# Lynx.net
KiCad netlist of a schematic drawn in EAGLE
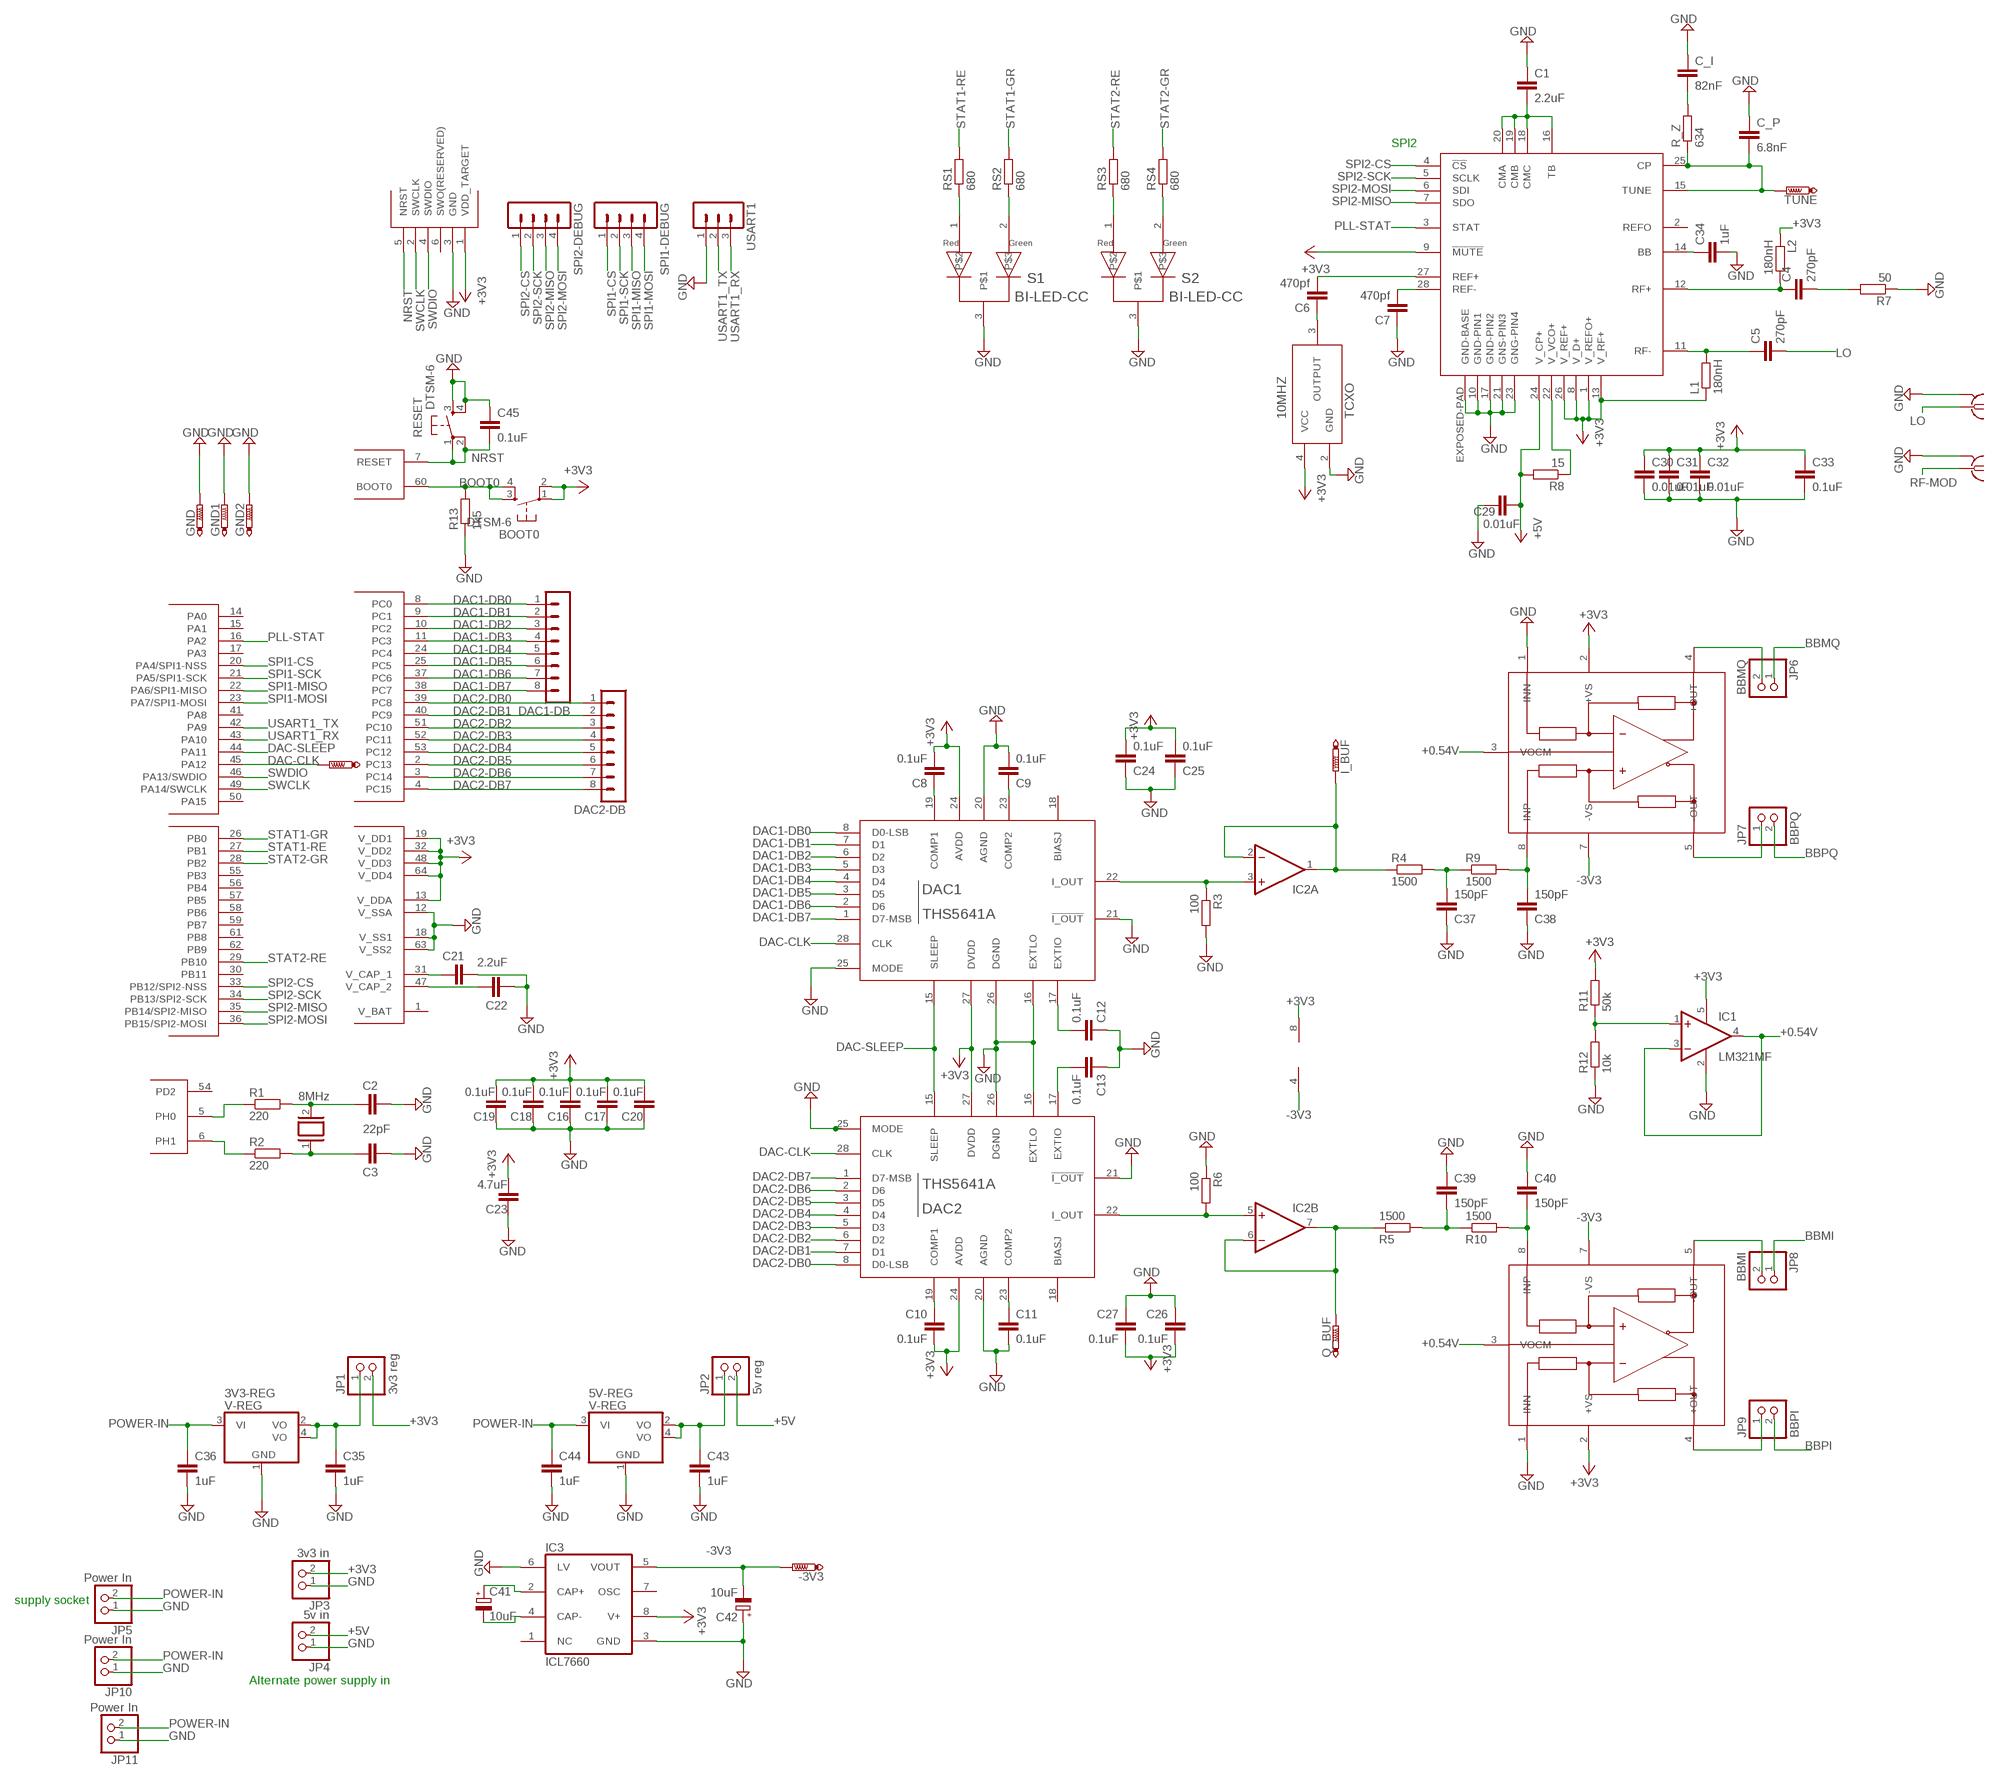
[diagram p0: schematic, sheet 1, part 1 of 2]
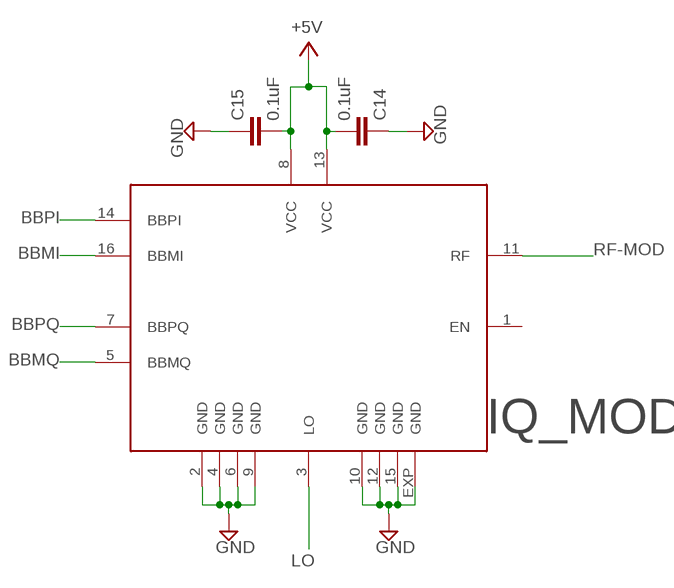
[diagram p1: schematic, sheet 1, part 2 of 2]

(export (version "E")
  (design (tool "Eeschema 10.0.6"))
  (components
    (comp (ref "-3V3")
      (value "PTR1PAD1-13Y")
      (footprint "eagle-import:P1-13Y")
      (libsource (lib "eagle-import") (part "PTR1PAD1-13Y"))
    )
    (comp (ref "3V3-REG")
      (value "V-REG")
      (footprint "eagle-import:SOT223")
      (libsource (lib "eagle-import") (part "VOLTAGE-REGULATOR"))
    )
    (comp (ref "5V-REG")
      (value "V-REG")
      (footprint "eagle-import:SOT223")
      (libsource (lib "eagle-import") (part "VOLTAGE-REGULATOR"))
    )
    (comp (ref "10MHZ")
      (value "TCXO")
      (footprint "eagle-import:TXCO5.6")
      (libsource (lib "eagle-import") (part "TCXO"))
    )
    (comp (ref "BOOT0")
      (value "DTSM-6")
      (footprint "eagle-import:DTSM-6")
      (libsource (lib "eagle-import") (part "DTSM-6"))
    )
    (comp (ref "C1")
      (value "2.2uF")
      (footprint "eagle-import:C0603")
      (libsource (lib "eagle-import") (part "C-EUC0603"))
    )
    (comp (ref "C2")
      (value "22pF")
      (footprint "eagle-import:C0603")
      (libsource (lib "eagle-import") (part "resistor_C-EUC0603"))
    )
    (comp (ref "C3")
      (value "22pF")
      (footprint "eagle-import:C0603")
      (libsource (lib "eagle-import") (part "resistor_C-EUC0603"))
    )
    (comp (ref "C4")
      (value "270pF")
      (footprint "eagle-import:C0805")
      (libsource (lib "eagle-import") (part "C-EUC0805"))
    )
    (comp (ref "C5")
      (value "270pF")
      (footprint "eagle-import:C0805")
      (libsource (lib "eagle-import") (part "C-EUC0805"))
    )
    (comp (ref "C6")
      (value "470pf")
      (footprint "eagle-import:C0402")
      (libsource (lib "eagle-import") (part "C-EUC0402"))
    )
    (comp (ref "C7")
      (value "470pf")
      (footprint "eagle-import:C0402")
      (libsource (lib "eagle-import") (part "C-EUC0402"))
    )
    (comp (ref "C8")
      (value "0.1uF")
      (footprint "eagle-import:C0603")
      (libsource (lib "eagle-import") (part "C-EUC0603"))
    )
    (comp (ref "C9")
      (value "0.1uF")
      (footprint "eagle-import:C0603")
      (libsource (lib "eagle-import") (part "C-EUC0603"))
    )
    (comp (ref "C10")
      (value "0.1uF")
      (footprint "eagle-import:C0603")
      (libsource (lib "eagle-import") (part "C-EUC0603"))
    )
    (comp (ref "C11")
      (value "0.1uF")
      (footprint "eagle-import:C0603")
      (libsource (lib "eagle-import") (part "C-EUC0603"))
    )
    (comp (ref "C12")
      (value "0.1uF")
      (footprint "eagle-import:C0603")
      (libsource (lib "eagle-import") (part "C-EUC0603"))
    )
    (comp (ref "C13")
      (value "0.1uF")
      (footprint "eagle-import:C0603")
      (libsource (lib "eagle-import") (part "C-EUC0603"))
    )
    (comp (ref "C14")
      (value "0.1uF")
      (footprint "eagle-import:C0603")
      (libsource (lib "eagle-import") (part "C-EUC0603"))
    )
    (comp (ref "C15")
      (value "0.1uF")
      (footprint "eagle-import:C0603")
      (libsource (lib "eagle-import") (part "C-EUC0603"))
    )
    (comp (ref "C16")
      (value "0.1uF")
      (footprint "eagle-import:C0603")
      (libsource (lib "eagle-import") (part "C-EUC0603"))
    )
    (comp (ref "C17")
      (value "0.1uF")
      (footprint "eagle-import:C0603")
      (libsource (lib "eagle-import") (part "C-EUC0603"))
    )
    (comp (ref "C18")
      (value "0.1uF")
      (footprint "eagle-import:C0603")
      (libsource (lib "eagle-import") (part "C-EUC0603"))
    )
    (comp (ref "C19")
      (value "0.1uF")
      (footprint "eagle-import:C0603")
      (libsource (lib "eagle-import") (part "C-EUC0603"))
    )
    (comp (ref "C20")
      (value "0.1uF")
      (footprint "eagle-import:C0603")
      (libsource (lib "eagle-import") (part "C-EUC0603"))
    )
    (comp (ref "C21")
      (value "2.2uF")
      (footprint "eagle-import:C0603")
      (libsource (lib "eagle-import") (part "resistor_C-EUC0603"))
    )
    (comp (ref "C22")
      (value "2.2uF")
      (footprint "eagle-import:C0603")
      (libsource (lib "eagle-import") (part "resistor_C-EUC0603"))
    )
    (comp (ref "C23")
      (value "4.7uF")
      (footprint "eagle-import:C0603")
      (libsource (lib "eagle-import") (part "C-EUC0603"))
    )
    (comp (ref "C24")
      (value "0.1uF")
      (footprint "eagle-import:C0603")
      (libsource (lib "eagle-import") (part "C-EUC0603"))
    )
    (comp (ref "C25")
      (value "0.1uF")
      (footprint "eagle-import:C0603")
      (libsource (lib "eagle-import") (part "C-EUC0603"))
    )
    (comp (ref "C26")
      (value "0.1uF")
      (footprint "eagle-import:C0603")
      (libsource (lib "eagle-import") (part "C-EUC0603"))
    )
    (comp (ref "C27")
      (value "0.1uF")
      (footprint "eagle-import:C0603")
      (libsource (lib "eagle-import") (part "C-EUC0603"))
    )
    (comp (ref "C29")
      (value "0.01uF")
      (footprint "eagle-import:C0603")
      (libsource (lib "eagle-import") (part "C-EUC0603"))
    )
    (comp (ref "C30")
      (value "0.01uF")
      (footprint "eagle-import:C0603")
      (libsource (lib "eagle-import") (part "C-EUC0603"))
    )
    (comp (ref "C31")
      (value "0.01uF")
      (footprint "eagle-import:C0402")
      (libsource (lib "eagle-import") (part "C-EUC0402"))
    )
    (comp (ref "C32")
      (value "0.01uF")
      (footprint "eagle-import:C0603")
      (libsource (lib "eagle-import") (part "C-EUC0603"))
    )
    (comp (ref "C33")
      (value "0.1uF")
      (footprint "eagle-import:C0603")
      (libsource (lib "eagle-import") (part "C-EUC0603"))
    )
    (comp (ref "C34")
      (value "1uF")
      (footprint "eagle-import:C0603")
      (libsource (lib "eagle-import") (part "C-EUC0603"))
    )
    (comp (ref "C35")
      (value "1uF")
      (footprint "eagle-import:C0603")
      (libsource (lib "eagle-import") (part "C-EUC0603"))
    )
    (comp (ref "C36")
      (value "1uF")
      (footprint "eagle-import:C0603")
      (libsource (lib "eagle-import") (part "C-EUC0603"))
    )
    (comp (ref "C37")
      (value "150pF")
      (footprint "eagle-import:C0603")
      (libsource (lib "eagle-import") (part "C-EUC0603"))
    )
    (comp (ref "C38")
      (value "150pF")
      (footprint "eagle-import:C0603")
      (libsource (lib "eagle-import") (part "C-EUC0603"))
    )
    (comp (ref "C39")
      (value "150pF")
      (footprint "eagle-import:C0603")
      (libsource (lib "eagle-import") (part "C-EUC0603"))
    )
    (comp (ref "C40")
      (value "150pF")
      (footprint "eagle-import:C0603")
      (libsource (lib "eagle-import") (part "C-EUC0603"))
    )
    (comp (ref "C41")
      (value "10uF")
      (footprint "eagle-import:SANYO-OSCON_SMD_B6")
      (libsource (lib "eagle-import") (part "CPOL-EUSANYO_SMD_B6"))
    )
    (comp (ref "C42")
      (value "10uF")
      (footprint "eagle-import:SANYO-OSCON_SMD_B6")
      (libsource (lib "eagle-import") (part "CPOL-EUSANYO_SMD_B6"))
    )
    (comp (ref "C43")
      (value "1uF")
      (footprint "eagle-import:C0603")
      (libsource (lib "eagle-import") (part "C-EUC0603"))
    )
    (comp (ref "C44")
      (value "1uF")
      (footprint "eagle-import:C0603")
      (libsource (lib "eagle-import") (part "C-EUC0603"))
    )
    (comp (ref "C45")
      (value "0.1uF")
      (footprint "eagle-import:C0603")
      (libsource (lib "eagle-import") (part "C-EUC0603"))
    )
    (comp (ref "C_I")
      (value "82nF")
      (footprint "eagle-import:C1210")
      (libsource (lib "eagle-import") (part "C-EUC1210"))
    )
    (comp (ref "C_P")
      (value "6.8nF")
      (footprint "eagle-import:C0805")
      (libsource (lib "eagle-import") (part "resistor_C-EUC0805"))
    )
    (comp (ref "DAC-CLK")
      (value "PTR1PAD1-13Y")
      (footprint "eagle-import:P1-13Y")
      (libsource (lib "eagle-import") (part "PTR1PAD1-13Y"))
    )
    (comp (ref "DAC1")
      (value "THS5641A")
      (footprint "eagle-import:SO28")
      (libsource (lib "eagle-import") (part "THS5641A"))
    )
    (comp (ref "DAC1-DB")
      (value "MA08-1")
      (footprint "eagle-import:MA08-1")
      (libsource (lib "eagle-import") (part "MA08-1"))
    )
    (comp (ref "DAC2")
      (value "THS5641A")
      (footprint "eagle-import:SO28")
      (libsource (lib "eagle-import") (part "THS5641A"))
    )
    (comp (ref "DAC2-DB")
      (value "MA08-1")
      (footprint "eagle-import:MA08-1")
      (libsource (lib "eagle-import") (part "MA08-1"))
    )
    (comp (ref "GND")
      (value "PTR1PAD1-13Y")
      (footprint "eagle-import:P1-13Y")
      (libsource (lib "eagle-import") (part "PTR1PAD1-13Y"))
    )
    (comp (ref "GND1")
      (value "PTR1PAD1-13Y")
      (footprint "eagle-import:P1-13Y")
      (libsource (lib "eagle-import") (part "PTR1PAD1-13Y"))
    )
    (comp (ref "GND2")
      (value "PTR1PAD1-13Y")
      (footprint "eagle-import:P1-13Y")
      (libsource (lib "eagle-import") (part "PTR1PAD1-13Y"))
    )
    (comp (ref "IC1")
      (value "LM321MF")
      (footprint "eagle-import:SOT23-5")
      (libsource (lib "eagle-import") (part "LM321?MF"))
    )
    (comp (ref "IC2")
      (value "2AMP_P8+4D")
      (footprint "eagle-import:SO08")
      (libsource (lib "eagle-import") (part "2AMP_P8+4D"))
    )
    (comp (ref "IC3")
      (value "ICL7660")
      (footprint "eagle-import:SO08")
      (fields (field (name "MF") "MAXIM") (field (name "MPN") "ICL7660CSA"))
      (libsource (lib "eagle-import") (part "ICL7660CSA"))
    )
    (comp (ref "IQ_MOD")
      (value "LT5568")
      (footprint "eagle-import:QFN-16")
      (libsource (lib "eagle-import") (part "LT5568"))
    )
    (comp (ref "I_BUF")
      (value "PTR1PAD1-13Y")
      (footprint "eagle-import:P1-13Y")
      (libsource (lib "eagle-import") (part "PTR1PAD1-13Y"))
    )
    (comp (ref "JP1")
      (value "3v3 reg")
      (footprint "eagle-import:1X02")
      (libsource (lib "eagle-import") (part "PINHD-1X2"))
    )
    (comp (ref "JP2")
      (value "5v reg")
      (footprint "eagle-import:1X02")
      (libsource (lib "eagle-import") (part "PINHD-1X2"))
    )
    (comp (ref "JP3")
      (value "3v3 in")
      (footprint "eagle-import:1X02")
      (libsource (lib "eagle-import") (part "PINHD-1X2"))
    )
    (comp (ref "JP4")
      (value "5v in")
      (footprint "eagle-import:1X02")
      (libsource (lib "eagle-import") (part "PINHD-1X2"))
    )
    (comp (ref "JP5")
      (value "Power In")
      (footprint "eagle-import:1X02")
      (libsource (lib "eagle-import") (part "PINHD-1X2"))
    )
    (comp (ref "JP6")
      (value "BBMQ")
      (footprint "eagle-import:1X02")
      (libsource (lib "eagle-import") (part "PINHD-1X2"))
    )
    (comp (ref "JP7")
      (value "BBPQ")
      (footprint "eagle-import:1X02")
      (libsource (lib "eagle-import") (part "PINHD-1X2"))
    )
    (comp (ref "JP8")
      (value "BBMI")
      (footprint "eagle-import:1X02")
      (libsource (lib "eagle-import") (part "PINHD-1X2"))
    )
    (comp (ref "JP9")
      (value "BBPI")
      (footprint "eagle-import:1X02")
      (libsource (lib "eagle-import") (part "PINHD-1X2"))
    )
    (comp (ref "JP10")
      (value "Power In")
      (footprint "eagle-import:1X02")
      (libsource (lib "eagle-import") (part "PINHD-1X2"))
    )
    (comp (ref "JP11")
      (value "Power In")
      (footprint "eagle-import:1X02")
      (libsource (lib "eagle-import") (part "PINHD-1X2"))
    )
    (comp (ref "L1")
      (value "180nH")
      (footprint "eagle-import:R0402")
      (libsource (lib "eagle-import") (part "R-EU_R0402"))
    )
    (comp (ref "L2")
      (value "180nH")
      (footprint "eagle-import:R0402")
      (libsource (lib "eagle-import") (part "R-EU_R0402"))
    )
    (comp (ref "LO")
      (value "SMA-142-0711-821/826")
      (footprint "eagle-import:J502-ND-142-0711-821_826")
      (fields (field (name "MF") "JOHNSON COMPONENTS") (field (name "MPN") "142-0711-821"))
      (libsource (lib "eagle-import") (part "SMA-142-0711-821/826"))
    )
    (comp (ref "Q1")
      (value "8MHz")
      (footprint "eagle-import:QS")
      (libsource (lib "eagle-import") (part "XTAL/S"))
    )
    (comp (ref "Q_BUF")
      (value "PTR1PAD1-13Y")
      (footprint "eagle-import:P1-13Y")
      (libsource (lib "eagle-import") (part "PTR1PAD1-13Y"))
    )
    (comp (ref "R1")
      (value "220")
      (footprint "eagle-import:R0603")
      (libsource (lib "eagle-import") (part "resistor_R-EU_R0603"))
    )
    (comp (ref "R2")
      (value "220")
      (footprint "eagle-import:R0603")
      (libsource (lib "eagle-import") (part "resistor_R-EU_R0603"))
    )
    (comp (ref "R3")
      (value "100")
      (footprint "eagle-import:R0603")
      (libsource (lib "eagle-import") (part "resistor_R-EU_R0603"))
    )
    (comp (ref "R4")
      (value "1500")
      (footprint "eagle-import:R0603")
      (libsource (lib "eagle-import") (part "resistor_R-EU_R0603"))
    )
    (comp (ref "R5")
      (value "1500")
      (footprint "eagle-import:R0603")
      (libsource (lib "eagle-import") (part "resistor_R-EU_R0603"))
    )
    (comp (ref "R6")
      (value "100")
      (footprint "eagle-import:R0603")
      (libsource (lib "eagle-import") (part "resistor_R-EU_R0603"))
    )
    (comp (ref "R7")
      (value "50")
      (footprint "eagle-import:R0805")
      (libsource (lib "eagle-import") (part "R-EU_R0805"))
    )
    (comp (ref "R8")
      (value "15")
      (footprint "eagle-import:R0603")
      (libsource (lib "eagle-import") (part "R-EU_R0603"))
    )
    (comp (ref "R9")
      (value "1500")
      (footprint "eagle-import:R0603")
      (libsource (lib "eagle-import") (part "resistor_R-EU_R0603"))
    )
    (comp (ref "R10")
      (value "1500")
      (footprint "eagle-import:R0603")
      (libsource (lib "eagle-import") (part "resistor_R-EU_R0603"))
    )
    (comp (ref "R11")
      (value "50k")
      (footprint "eagle-import:R0603")
      (libsource (lib "eagle-import") (part "resistor_R-EU_R0603"))
    )
    (comp (ref "R12")
      (value "10k")
      (footprint "eagle-import:R0603")
      (libsource (lib "eagle-import") (part "resistor_R-EU_R0603"))
    )
    (comp (ref "R13")
      (value "1k5")
      (footprint "eagle-import:R0603")
      (libsource (lib "eagle-import") (part "resistor_R-EU_R0603"))
    )
    (comp (ref "RESET")
      (value "DTSM-6")
      (footprint "eagle-import:DTSM-6")
      (libsource (lib "eagle-import") (part "DTSM-6"))
    )
    (comp (ref "RF-MOD")
      (value "SMA-142-0711-821/826")
      (footprint "eagle-import:J502-ND-142-0711-821_826")
      (fields (field (name "MF") "JOHNSON COMPONENTS") (field (name "MPN") "142-0711-821"))
      (libsource (lib "eagle-import") (part "SMA-142-0711-821/826"))
    )
    (comp (ref "RS1")
      (value "680")
      (footprint "eagle-import:R0603")
      (libsource (lib "eagle-import") (part "resistor_R-EU_R0603"))
    )
    (comp (ref "RS2")
      (value "680")
      (footprint "eagle-import:R0603")
      (libsource (lib "eagle-import") (part "resistor_R-EU_R0603"))
    )
    (comp (ref "RS3")
      (value "680")
      (footprint "eagle-import:R0603")
      (libsource (lib "eagle-import") (part "resistor_R-EU_R0603"))
    )
    (comp (ref "RS4")
      (value "680")
      (footprint "eagle-import:R0603")
      (libsource (lib "eagle-import") (part "resistor_R-EU_R0603"))
    )
    (comp (ref "R_Z")
      (value "634")
      (footprint "eagle-import:R0805")
      (libsource (lib "eagle-import") (part "R-EU_R0805"))
    )
    (comp (ref "S1")
      (value "BI-LED-CC")
      (footprint "eagle-import:SOT-23")
      (libsource (lib "eagle-import") (part "BI-LED-CC"))
    )
    (comp (ref "S2")
      (value "BI-LED-CC")
      (footprint "eagle-import:SOT-23")
      (libsource (lib "eagle-import") (part "BI-LED-CC"))
    )
    (comp (ref "SPI1-DEBUG")
      (value "MA04-1")
      (footprint "eagle-import:MA04-1")
      (libsource (lib "eagle-import") (part "MA04-1"))
    )
    (comp (ref "SPI2-DEBUG")
      (value "MA04-1")
      (footprint "eagle-import:MA04-1")
      (libsource (lib "eagle-import") (part "MA04-1"))
    )
    (comp (ref "SWD-HEADER")
      (value "SWD-HEADER")
      (footprint "eagle-import:6PIN-HEADER")
      (libsource (lib "eagle-import") (part "SWD-HEADER"))
    )
    (comp (ref "TUNE")
      (value "PTR1B1,27")
      (footprint "eagle-import:B1,27")
      (libsource (lib "eagle-import") (part "PTR1B1,27"))
    )
    (comp (ref "U$1")
      (value "STM32F415RGT6")
      (footprint "eagle-import:LQFP-64")
      (libsource (lib "eagle-import") (part "STM32F415RGT6"))
    )
    (comp (ref "U$3")
      (value "LTC6946")
      (footprint "eagle-import:QFN-28")
      (libsource (lib "eagle-import") (part "LTC6946"))
    )
    (comp (ref "U$4")
      (value "AD8476")
      (footprint "eagle-import:MSOP8")
      (libsource (lib "eagle-import") (part "AD8476"))
    )
    (comp (ref "U$5")
      (value "AD8476")
      (footprint "eagle-import:MSOP8")
      (libsource (lib "eagle-import") (part "AD8476"))
    )
    (comp (ref "USART1")
      (value "MA03-1")
      (footprint "eagle-import:MA03-1")
      (libsource (lib "eagle-import") (part "MA03-1"))
    )
  )
  (nets
    (net (code "1") (name "+3V3") (class "Default")
      (node (ref "10MHZ") (pin "4") (pinfunction "VCC_4") (pintype "power_in"))
      (node (ref "BOOT0") (pin "1") (pinfunction "1_1") (pintype "passive"))
      (node (ref "BOOT0") (pin "2") (pinfunction "2_2") (pintype "passive"))
      (node (ref "C10") (pin "2") (pinfunction "2_2") (pintype "passive"))
      (node (ref "C16") (pin "2") (pinfunction "2_2") (pintype "passive"))
      (node (ref "C17") (pin "2") (pinfunction "2_2") (pintype "passive"))
      (node (ref "C18") (pin "2") (pinfunction "2_2") (pintype "passive"))
      (node (ref "C19") (pin "2") (pinfunction "2_2") (pintype "passive"))
      (node (ref "C20") (pin "2") (pinfunction "2_2") (pintype "passive"))
      (node (ref "C23") (pin "2") (pinfunction "2_2") (pintype "passive"))
      (node (ref "C24") (pin "2") (pinfunction "2_2") (pintype "passive"))
      (node (ref "C25") (pin "2") (pinfunction "2_2") (pintype "passive"))
      (node (ref "C26") (pin "2") (pinfunction "2_2") (pintype "passive"))
      (node (ref "C27") (pin "2") (pinfunction "2_2") (pintype "passive"))
      (node (ref "C30") (pin "1") (pinfunction "1_1") (pintype "passive"))
      (node (ref "C31") (pin "1") (pinfunction "1_1") (pintype "passive"))
      (node (ref "C32") (pin "1") (pinfunction "1_1") (pintype "passive"))
      (node (ref "C33") (pin "1") (pinfunction "1_1") (pintype "passive"))
      (node (ref "C8") (pin "2") (pinfunction "2_2") (pintype "passive"))
      (node (ref "DAC1") (pin "24") (pinfunction "AVDD_24") (pintype "bidirectional"))
      (node (ref "DAC1") (pin "27") (pinfunction "DVDD_27") (pintype "bidirectional"))
      (node (ref "DAC2") (pin "24") (pinfunction "AVDD_24") (pintype "bidirectional"))
      (node (ref "DAC2") (pin "27") (pinfunction "DVDD_27") (pintype "bidirectional"))
      (node (ref "IC1") (pin "5") (pinfunction "V+_5") (pintype "power_in"))
      (node (ref "IC2") (pin "8") (pinfunction "V+_8") (pintype "power_in"))
      (node (ref "IC3") (pin "8") (pinfunction "V+_8") (pintype "power_in"))
      (node (ref "JP1") (pin "2") (pinfunction "2_2") (pintype "passive"))
      (node (ref "JP3") (pin "2") (pinfunction "2_2") (pintype "passive"))
      (node (ref "L1") (pin "1") (pinfunction "1_1") (pintype "passive"))
      (node (ref "L2") (pin "1") (pinfunction "1_1") (pintype "passive"))
      (node (ref "R11") (pin "2") (pinfunction "2_2") (pintype "passive"))
      (node (ref "SWD-HEADER") (pin "1") (pinfunction "VDD_TARGET_1") (pintype "bidirectional"))
      (node (ref "U$1") (pin "13") (pinfunction "V_DDA_13") (pintype "bidirectional"))
      (node (ref "U$1") (pin "19") (pinfunction "V_DD1_19") (pintype "bidirectional"))
      (node (ref "U$1") (pin "32") (pinfunction "V_DD2_32") (pintype "bidirectional"))
      (node (ref "U$1") (pin "48") (pinfunction "V_DD3_48") (pintype "bidirectional"))
      (node (ref "U$1") (pin "64") (pinfunction "V_DD4_64") (pintype "bidirectional"))
      (node (ref "U$3") (pin "1") (pinfunction "V_REFO+_1") (pintype "bidirectional"))
      (node (ref "U$3") (pin "13") (pinfunction "V_RF+_13") (pintype "bidirectional"))
      (node (ref "U$3") (pin "26") (pinfunction "V_REF+_26") (pintype "bidirectional"))
      (node (ref "U$3") (pin "8") (pinfunction "V_D+_8") (pintype "bidirectional"))
      (node (ref "U$3") (pin "9") (pinfunction "~{MUTE}_9") (pintype "bidirectional"))
      (node (ref "U$4") (pin "2") (pinfunction "+VS_2") (pintype "bidirectional"))
      (node (ref "U$5") (pin "2") (pinfunction "+VS_2") (pintype "bidirectional"))
    )
    (net (code "2") (name "+5V") (class "Default")
      (node (ref "C14") (pin "2") (pinfunction "2_2") (pintype "passive"))
      (node (ref "C15") (pin "2") (pinfunction "2_2") (pintype "passive"))
      (node (ref "C29") (pin "2") (pinfunction "2_2") (pintype "passive"))
      (node (ref "IQ_MOD") (pin "13") (pinfunction "VCC_13") (pintype "bidirectional"))
      (node (ref "IQ_MOD") (pin "8") (pinfunction "VCC_8") (pintype "bidirectional"))
      (node (ref "JP2") (pin "2") (pinfunction "2_2") (pintype "passive"))
      (node (ref "JP4") (pin "2") (pinfunction "2_2") (pintype "passive"))
      (node (ref "R8") (pin "2") (pinfunction "2_2") (pintype "passive"))
      (node (ref "U$3") (pin "24") (pinfunction "V_CP+_24") (pintype "bidirectional"))
    )
    (net (code "3") (name "/+0.54V") (class "Default")
      (node (ref "IC1") (pin "3") (pinfunction "-IN_3") (pintype "input"))
      (node (ref "IC1") (pin "4") (pinfunction "OUT_4") (pintype "output"))
      (node (ref "U$4") (pin "3") (pinfunction "VOCM_3") (pintype "bidirectional"))
      (node (ref "U$5") (pin "3") (pinfunction "VOCM_3") (pintype "bidirectional"))
    )
    (net (code "4") (name "/-3V3") (class "Default")
      (node (ref "-3V3") (pin "TP") (pinfunction "TP_TP") (pintype "input"))
      (node (ref "C42") (pin "-") (pinfunction "-_-") (pintype "passive"))
      (node (ref "IC2") (pin "4") (pinfunction "V-_4") (pintype "power_in"))
      (node (ref "IC3") (pin "5") (pinfunction "VOUT_5") (pintype "output"))
      (node (ref "U$4") (pin "7") (pinfunction "-VS_7") (pintype "bidirectional"))
      (node (ref "U$5") (pin "7") (pinfunction "-VS_7") (pintype "bidirectional"))
    )
    (net (code "5") (name "/BBMI") (class "Default")
      (node (ref "IQ_MOD") (pin "16") (pinfunction "BBMI_16") (pintype "bidirectional"))
      (node (ref "JP8") (pin "1") (pinfunction "1_1") (pintype "passive"))
    )
    (net (code "6") (name "/BBMQ") (class "Default")
      (node (ref "IQ_MOD") (pin "5") (pinfunction "BBMQ_5") (pintype "bidirectional"))
      (node (ref "JP6") (pin "1") (pinfunction "1_1") (pintype "passive"))
    )
    (net (code "7") (name "/BBPI") (class "Default")
      (node (ref "IQ_MOD") (pin "14") (pinfunction "BBPI_14") (pintype "bidirectional"))
      (node (ref "JP9") (pin "2") (pinfunction "2_2") (pintype "passive"))
    )
    (net (code "8") (name "/BBPQ") (class "Default")
      (node (ref "IQ_MOD") (pin "7") (pinfunction "BBPQ_7") (pintype "bidirectional"))
      (node (ref "JP7") (pin "2") (pinfunction "2_2") (pintype "passive"))
    )
    (net (code "9") (name "/BOOT0") (class "Default")
      (node (ref "BOOT0") (pin "3") (pinfunction "3_3") (pintype "passive"))
      (node (ref "BOOT0") (pin "4") (pinfunction "4_4") (pintype "passive"))
      (node (ref "R13") (pin "2") (pinfunction "2_2") (pintype "passive"))
      (node (ref "U$1") (pin "60") (pinfunction "BOOT0_60") (pintype "bidirectional"))
    )
    (net (code "10") (name "/DAC-CLK") (class "Default")
      (node (ref "DAC-CLK") (pin "TP") (pinfunction "TP_TP") (pintype "input"))
      (node (ref "DAC1") (pin "28") (pinfunction "CLK_28") (pintype "bidirectional"))
      (node (ref "DAC2") (pin "28") (pinfunction "CLK_28") (pintype "bidirectional"))
      (node (ref "U$1") (pin "45") (pinfunction "PA12_45") (pintype "bidirectional"))
    )
    (net (code "11") (name "/DAC-SLEEP") (class "Default")
      (node (ref "DAC1") (pin "15") (pinfunction "SLEEP_15") (pintype "bidirectional"))
      (node (ref "DAC2") (pin "15") (pinfunction "SLEEP_15") (pintype "bidirectional"))
      (node (ref "U$1") (pin "44") (pinfunction "PA11_44") (pintype "bidirectional"))
    )
    (net (code "12") (name "/DAC1-DB0") (class "Default")
      (node (ref "DAC1") (pin "8") (pinfunction "D0-LSB_8") (pintype "bidirectional"))
      (node (ref "DAC1-DB") (pin "1") (pinfunction "1_1") (pintype "passive"))
      (node (ref "U$1") (pin "8") (pinfunction "PC0_8") (pintype "bidirectional"))
    )
    (net (code "13") (name "/DAC1-DB1") (class "Default")
      (node (ref "DAC1") (pin "7") (pinfunction "D1_7") (pintype "bidirectional"))
      (node (ref "DAC1-DB") (pin "2") (pinfunction "2_2") (pintype "passive"))
      (node (ref "U$1") (pin "9") (pinfunction "PC1_9") (pintype "bidirectional"))
    )
    (net (code "14") (name "/DAC1-DB2") (class "Default")
      (node (ref "DAC1") (pin "6") (pinfunction "D2_6") (pintype "bidirectional"))
      (node (ref "DAC1-DB") (pin "3") (pinfunction "3_3") (pintype "passive"))
      (node (ref "U$1") (pin "10") (pinfunction "PC2_10") (pintype "bidirectional"))
    )
    (net (code "15") (name "/DAC1-DB3") (class "Default")
      (node (ref "DAC1") (pin "5") (pinfunction "D3_5") (pintype "bidirectional"))
      (node (ref "DAC1-DB") (pin "4") (pinfunction "4_4") (pintype "passive"))
      (node (ref "U$1") (pin "11") (pinfunction "PC3_11") (pintype "bidirectional"))
    )
    (net (code "16") (name "/DAC1-DB4") (class "Default")
      (node (ref "DAC1") (pin "4") (pinfunction "D4_4") (pintype "bidirectional"))
      (node (ref "DAC1-DB") (pin "5") (pinfunction "5_5") (pintype "passive"))
      (node (ref "U$1") (pin "24") (pinfunction "PC4_24") (pintype "bidirectional"))
    )
    (net (code "17") (name "/DAC1-DB5") (class "Default")
      (node (ref "DAC1") (pin "3") (pinfunction "D5_3") (pintype "bidirectional"))
      (node (ref "DAC1-DB") (pin "6") (pinfunction "6_6") (pintype "passive"))
      (node (ref "U$1") (pin "25") (pinfunction "PC5_25") (pintype "bidirectional"))
    )
    (net (code "18") (name "/DAC1-DB6") (class "Default")
      (node (ref "DAC1") (pin "2") (pinfunction "D6_2") (pintype "bidirectional"))
      (node (ref "DAC1-DB") (pin "7") (pinfunction "7_7") (pintype "passive"))
      (node (ref "U$1") (pin "37") (pinfunction "PC6_37") (pintype "bidirectional"))
    )
    (net (code "19") (name "/DAC1-DB7") (class "Default")
      (node (ref "DAC1") (pin "1") (pinfunction "D7-MSB_1") (pintype "bidirectional"))
      (node (ref "DAC1-DB") (pin "8") (pinfunction "8_8") (pintype "passive"))
      (node (ref "U$1") (pin "38") (pinfunction "PC7_38") (pintype "bidirectional"))
    )
    (net (code "20") (name "/DAC2-DB0") (class "Default")
      (node (ref "DAC2") (pin "8") (pinfunction "D0-LSB_8") (pintype "bidirectional"))
      (node (ref "DAC2-DB") (pin "1") (pinfunction "1_1") (pintype "passive"))
      (node (ref "U$1") (pin "39") (pinfunction "PC8_39") (pintype "bidirectional"))
    )
    (net (code "21") (name "/DAC2-DB1") (class "Default")
      (node (ref "DAC2") (pin "7") (pinfunction "D1_7") (pintype "bidirectional"))
      (node (ref "DAC2-DB") (pin "2") (pinfunction "2_2") (pintype "passive"))
      (node (ref "U$1") (pin "40") (pinfunction "PC9_40") (pintype "bidirectional"))
    )
    (net (code "22") (name "/DAC2-DB2") (class "Default")
      (node (ref "DAC2") (pin "6") (pinfunction "D2_6") (pintype "bidirectional"))
      (node (ref "DAC2-DB") (pin "3") (pinfunction "3_3") (pintype "passive"))
      (node (ref "U$1") (pin "51") (pinfunction "PC10_51") (pintype "bidirectional"))
    )
    (net (code "23") (name "/DAC2-DB3") (class "Default")
      (node (ref "DAC2") (pin "5") (pinfunction "D3_5") (pintype "bidirectional"))
      (node (ref "DAC2-DB") (pin "4") (pinfunction "4_4") (pintype "passive"))
      (node (ref "U$1") (pin "52") (pinfunction "PC11_52") (pintype "bidirectional"))
    )
    (net (code "24") (name "/DAC2-DB4") (class "Default")
      (node (ref "DAC2") (pin "4") (pinfunction "D4_4") (pintype "bidirectional"))
      (node (ref "DAC2-DB") (pin "5") (pinfunction "5_5") (pintype "passive"))
      (node (ref "U$1") (pin "53") (pinfunction "PC12_53") (pintype "bidirectional"))
    )
    (net (code "25") (name "/DAC2-DB5") (class "Default")
      (node (ref "DAC2") (pin "3") (pinfunction "D5_3") (pintype "bidirectional"))
      (node (ref "DAC2-DB") (pin "6") (pinfunction "6_6") (pintype "passive"))
      (node (ref "U$1") (pin "2") (pinfunction "PC13_2") (pintype "bidirectional"))
    )
    (net (code "26") (name "/DAC2-DB6") (class "Default")
      (node (ref "DAC2") (pin "2") (pinfunction "D6_2") (pintype "bidirectional"))
      (node (ref "DAC2-DB") (pin "7") (pinfunction "7_7") (pintype "passive"))
      (node (ref "U$1") (pin "3") (pinfunction "PC14_3") (pintype "bidirectional"))
    )
    (net (code "27") (name "/DAC2-DB7") (class "Default")
      (node (ref "DAC2") (pin "1") (pinfunction "D7-MSB_1") (pintype "bidirectional"))
      (node (ref "DAC2-DB") (pin "8") (pinfunction "8_8") (pintype "passive"))
      (node (ref "U$1") (pin "4") (pinfunction "PC15_4") (pintype "bidirectional"))
    )
    (net (code "28") (name "/LO") (class "Default")
      (node (ref "C5") (pin "2") (pinfunction "2_2") (pintype "passive"))
      (node (ref "IQ_MOD") (pin "3") (pinfunction "LO_3") (pintype "bidirectional"))
      (node (ref "LO") (pin "1") (pinfunction "1_1") (pintype "passive"))
    )
    (net (code "29") (name "/NRST") (class "Default")
      (node (ref "C45") (pin "2") (pinfunction "2_2") (pintype "passive"))
      (node (ref "RESET") (pin "1") (pinfunction "1_1") (pintype "passive"))
      (node (ref "RESET") (pin "2") (pinfunction "2_2") (pintype "passive"))
      (node (ref "SWD-HEADER") (pin "5") (pinfunction "NRST_5") (pintype "bidirectional"))
      (node (ref "U$1") (pin "7") (pinfunction "RESET_7") (pintype "bidirectional"))
    )
    (net (code "30") (name "/PLL-STAT") (class "Default")
      (node (ref "U$1") (pin "16") (pinfunction "PA2_16") (pintype "bidirectional"))
      (node (ref "U$3") (pin "3") (pinfunction "STAT_3") (pintype "bidirectional"))
    )
    (net (code "31") (name "/POWER-IN") (class "Default")
      (node (ref "3V3-REG") (pin "3") (pinfunction "VI_3") (pintype "input"))
      (node (ref "5V-REG") (pin "3") (pinfunction "VI_3") (pintype "input"))
      (node (ref "C36") (pin "1") (pinfunction "1_1") (pintype "passive"))
      (node (ref "C44") (pin "1") (pinfunction "1_1") (pintype "passive"))
      (node (ref "JP10") (pin "2") (pinfunction "2_2") (pintype "passive"))
      (node (ref "JP11") (pin "2") (pinfunction "2_2") (pintype "passive"))
      (node (ref "JP5") (pin "2") (pinfunction "2_2") (pintype "passive"))
    )
    (net (code "32") (name "/RF-MOD") (class "Default")
      (node (ref "IQ_MOD") (pin "11") (pinfunction "RF_11") (pintype "bidirectional"))
      (node (ref "RF-MOD") (pin "1") (pinfunction "1_1") (pintype "passive"))
    )
    (net (code "33") (name "/SPI1-CS") (class "Default")
      (node (ref "SPI1-DEBUG") (pin "1") (pinfunction "1_1") (pintype "passive"))
      (node (ref "U$1") (pin "20") (pinfunction "PA4/SPI1-NSS_20") (pintype "bidirectional"))
    )
    (net (code "34") (name "/SPI1-MISO") (class "Default")
      (node (ref "SPI1-DEBUG") (pin "3") (pinfunction "3_3") (pintype "passive"))
      (node (ref "U$1") (pin "22") (pinfunction "PA6/SPI1-MISO_22") (pintype "bidirectional"))
    )
    (net (code "35") (name "/SPI1-MOSI") (class "Default")
      (node (ref "SPI1-DEBUG") (pin "4") (pinfunction "4_4") (pintype "passive"))
      (node (ref "U$1") (pin "23") (pinfunction "PA7/SPI1-MOSI_23") (pintype "bidirectional"))
    )
    (net (code "36") (name "/SPI1-SCK") (class "Default")
      (node (ref "SPI1-DEBUG") (pin "2") (pinfunction "2_2") (pintype "passive"))
      (node (ref "U$1") (pin "21") (pinfunction "PA5/SPI1-SCK_21") (pintype "bidirectional"))
    )
    (net (code "37") (name "/SPI2-CS") (class "Default")
      (node (ref "SPI2-DEBUG") (pin "1") (pinfunction "1_1") (pintype "passive"))
      (node (ref "U$1") (pin "33") (pinfunction "PB12/SPI2-NSS_33") (pintype "bidirectional"))
      (node (ref "U$3") (pin "4") (pinfunction "~{CS}_4") (pintype "bidirectional"))
    )
    (net (code "38") (name "/SPI2-MISO") (class "Default")
      (node (ref "SPI2-DEBUG") (pin "3") (pinfunction "3_3") (pintype "passive"))
      (node (ref "U$1") (pin "35") (pinfunction "PB14/SPI2-MISO_35") (pintype "bidirectional"))
      (node (ref "U$3") (pin "7") (pinfunction "SDO_7") (pintype "bidirectional"))
    )
    (net (code "39") (name "/SPI2-MOSI") (class "Default")
      (node (ref "SPI2-DEBUG") (pin "4") (pinfunction "4_4") (pintype "passive"))
      (node (ref "U$1") (pin "36") (pinfunction "PB15/SPI2-MOSI_36") (pintype "bidirectional"))
      (node (ref "U$3") (pin "6") (pinfunction "SDI_6") (pintype "bidirectional"))
    )
    (net (code "40") (name "/SPI2-SCK") (class "Default")
      (node (ref "SPI2-DEBUG") (pin "2") (pinfunction "2_2") (pintype "passive"))
      (node (ref "U$1") (pin "34") (pinfunction "PB13/SPI2-SCK_34") (pintype "bidirectional"))
      (node (ref "U$3") (pin "5") (pinfunction "SCLK_5") (pintype "bidirectional"))
    )
    (net (code "41") (name "/STAT1-GR") (class "Default")
      (node (ref "RS2") (pin "2") (pinfunction "2_2") (pintype "passive"))
      (node (ref "U$1") (pin "26") (pinfunction "PB0_26") (pintype "bidirectional"))
    )
    (net (code "42") (name "/STAT1-RE") (class "Default")
      (node (ref "RS1") (pin "2") (pinfunction "2_2") (pintype "passive"))
      (node (ref "U$1") (pin "27") (pinfunction "PB1_27") (pintype "bidirectional"))
    )
    (net (code "43") (name "/STAT2-GR") (class "Default")
      (node (ref "RS4") (pin "2") (pinfunction "2_2") (pintype "passive"))
      (node (ref "U$1") (pin "28") (pinfunction "PB2_28") (pintype "bidirectional"))
    )
    (net (code "44") (name "/STAT2-RE") (class "Default")
      (node (ref "RS3") (pin "2") (pinfunction "2_2") (pintype "passive"))
      (node (ref "U$1") (pin "29") (pinfunction "PB10_29") (pintype "bidirectional"))
    )
    (net (code "45") (name "/SWCLK") (class "Default")
      (node (ref "SWD-HEADER") (pin "2") (pinfunction "SWCLK_2") (pintype "bidirectional"))
      (node (ref "U$1") (pin "49") (pinfunction "PA14/SWCLK_49") (pintype "bidirectional"))
    )
    (net (code "46") (name "/SWDIO") (class "Default")
      (node (ref "SWD-HEADER") (pin "4") (pinfunction "SWDIO_4") (pintype "bidirectional"))
      (node (ref "U$1") (pin "46") (pinfunction "PA13/SWDIO_46") (pintype "bidirectional"))
    )
    (net (code "47") (name "/USART1_RX") (class "Default")
      (node (ref "U$1") (pin "43") (pinfunction "PA10_43") (pintype "bidirectional"))
      (node (ref "USART1") (pin "3") (pinfunction "3_3") (pintype "passive"))
    )
    (net (code "48") (name "/USART1_TX") (class "Default")
      (node (ref "U$1") (pin "42") (pinfunction "PA9_42") (pintype "bidirectional"))
      (node (ref "USART1") (pin "2") (pinfunction "2_2") (pintype "passive"))
    )
    (net (code "49") (name "GND") (class "Default")
      (node (ref "10MHZ") (pin "2") (pinfunction "GND_2") (pintype "power_in"))
      (node (ref "3V3-REG") (pin "1") (pinfunction "GND_1") (pintype "passive"))
      (node (ref "5V-REG") (pin "1") (pinfunction "GND_1") (pintype "passive"))
      (node (ref "C1") (pin "1") (pinfunction "1_1") (pintype "passive"))
      (node (ref "C11") (pin "2") (pinfunction "2_2") (pintype "passive"))
      (node (ref "C12") (pin "1") (pinfunction "1_1") (pintype "passive"))
      (node (ref "C13") (pin "1") (pinfunction "1_1") (pintype "passive"))
      (node (ref "C14") (pin "1") (pinfunction "1_1") (pintype "passive"))
      (node (ref "C15") (pin "1") (pinfunction "1_1") (pintype "passive"))
      (node (ref "C16") (pin "1") (pinfunction "1_1") (pintype "passive"))
      (node (ref "C17") (pin "1") (pinfunction "1_1") (pintype "passive"))
      (node (ref "C18") (pin "1") (pinfunction "1_1") (pintype "passive"))
      (node (ref "C19") (pin "1") (pinfunction "1_1") (pintype "passive"))
      (node (ref "C2") (pin "2") (pinfunction "2_2") (pintype "passive"))
      (node (ref "C20") (pin "1") (pinfunction "1_1") (pintype "passive"))
      (node (ref "C21") (pin "2") (pinfunction "2_2") (pintype "passive"))
      (node (ref "C22") (pin "2") (pinfunction "2_2") (pintype "passive"))
      (node (ref "C23") (pin "1") (pinfunction "1_1") (pintype "passive"))
      (node (ref "C24") (pin "1") (pinfunction "1_1") (pintype "passive"))
      (node (ref "C25") (pin "1") (pinfunction "1_1") (pintype "passive"))
      (node (ref "C26") (pin "1") (pinfunction "1_1") (pintype "passive"))
      (node (ref "C27") (pin "1") (pinfunction "1_1") (pintype "passive"))
      (node (ref "C29") (pin "1") (pinfunction "1_1") (pintype "passive"))
      (node (ref "C3") (pin "2") (pinfunction "2_2") (pintype "passive"))
      (node (ref "C30") (pin "2") (pinfunction "2_2") (pintype "passive"))
      (node (ref "C31") (pin "2") (pinfunction "2_2") (pintype "passive"))
      (node (ref "C32") (pin "2") (pinfunction "2_2") (pintype "passive"))
      (node (ref "C33") (pin "2") (pinfunction "2_2") (pintype "passive"))
      (node (ref "C34") (pin "2") (pinfunction "2_2") (pintype "passive"))
      (node (ref "C35") (pin "2") (pinfunction "2_2") (pintype "passive"))
      (node (ref "C36") (pin "2") (pinfunction "2_2") (pintype "passive"))
      (node (ref "C37") (pin "1") (pinfunction "1_1") (pintype "passive"))
      (node (ref "C38") (pin "1") (pinfunction "1_1") (pintype "passive"))
      (node (ref "C39") (pin "1") (pinfunction "1_1") (pintype "passive"))
      (node (ref "C40") (pin "1") (pinfunction "1_1") (pintype "passive"))
      (node (ref "C42") (pin "+") (pinfunction "+_+") (pintype "passive"))
      (node (ref "C43") (pin "2") (pinfunction "2_2") (pintype "passive"))
      (node (ref "C44") (pin "2") (pinfunction "2_2") (pintype "passive"))
      (node (ref "C45") (pin "1") (pinfunction "1_1") (pintype "passive"))
      (node (ref "C7") (pin "1") (pinfunction "1_1") (pintype "passive"))
      (node (ref "C9") (pin "2") (pinfunction "2_2") (pintype "passive"))
      (node (ref "C_I") (pin "1") (pinfunction "1_1") (pintype "passive"))
      (node (ref "C_P") (pin "1") (pinfunction "1_1") (pintype "passive"))
      (node (ref "DAC1") (pin "16") (pinfunction "EXTLO_16") (pintype "bidirectional"))
      (node (ref "DAC1") (pin "20") (pinfunction "AGND_20") (pintype "bidirectional"))
      (node (ref "DAC1") (pin "21") (pinfunction "~{I_OUT}_21") (pintype "bidirectional"))
      (node (ref "DAC1") (pin "25") (pinfunction "MODE_25") (pintype "bidirectional"))
      (node (ref "DAC1") (pin "26") (pinfunction "DGND_26") (pintype "bidirectional"))
      (node (ref "DAC2") (pin "16") (pinfunction "EXTLO_16") (pintype "bidirectional"))
      (node (ref "DAC2") (pin "20") (pinfunction "AGND_20") (pintype "bidirectional"))
      (node (ref "DAC2") (pin "21") (pinfunction "~{I_OUT}_21") (pintype "bidirectional"))
      (node (ref "DAC2") (pin "25") (pinfunction "MODE_25") (pintype "bidirectional"))
      (node (ref "DAC2") (pin "26") (pinfunction "DGND_26") (pintype "bidirectional"))
      (node (ref "GND") (pin "TP") (pinfunction "TP_TP") (pintype "input"))
      (node (ref "GND1") (pin "TP") (pinfunction "TP_TP") (pintype "input"))
      (node (ref "GND2") (pin "TP") (pinfunction "TP_TP") (pintype "input"))
      (node (ref "IC1") (pin "2") (pinfunction "V-_2") (pintype "power_in"))
      (node (ref "IC3") (pin "3") (pinfunction "GND_3") (pintype "power_in"))
      (node (ref "IC3") (pin "6") (pinfunction "LV_6") (pintype "passive"))
      (node (ref "IQ_MOD") (pin "10") (pinfunction "GND_10") (pintype "bidirectional"))
      (node (ref "IQ_MOD") (pin "12") (pinfunction "GND_12") (pintype "bidirectional"))
      (node (ref "IQ_MOD") (pin "15") (pinfunction "GND_15") (pintype "bidirectional"))
      (node (ref "IQ_MOD") (pin "2") (pinfunction "GND_2") (pintype "bidirectional"))
      (node (ref "IQ_MOD") (pin "4") (pinfunction "GND_4") (pintype "bidirectional"))
      (node (ref "IQ_MOD") (pin "6") (pinfunction "GND_6") (pintype "bidirectional"))
      (node (ref "IQ_MOD") (pin "9") (pinfunction "GND_9") (pintype "bidirectional"))
      (node (ref "IQ_MOD") (pin "EXP") (pinfunction "GND_EXP") (pintype "bidirectional"))
      (node (ref "JP10") (pin "1") (pinfunction "1_1") (pintype "passive"))
      (node (ref "JP11") (pin "1") (pinfunction "1_1") (pintype "passive"))
      (node (ref "JP3") (pin "1") (pinfunction "1_1") (pintype "passive"))
      (node (ref "JP4") (pin "1") (pinfunction "1_1") (pintype "passive"))
      (node (ref "JP5") (pin "1") (pinfunction "1_1") (pintype "passive"))
      (node (ref "LO") (pin "G@1") (pinfunction "2_G@1") (pintype "passive"))
      (node (ref "LO") (pin "G@2") (pinfunction "2_G@2") (pintype "passive"))
      (node (ref "LO") (pin "G@3") (pinfunction "2_G@3") (pintype "passive"))
      (node (ref "LO") (pin "G@4") (pinfunction "2_G@4") (pintype "passive"))
      (node (ref "R12") (pin "1") (pinfunction "1_1") (pintype "passive"))
      (node (ref "R13") (pin "1") (pinfunction "1_1") (pintype "passive"))
      (node (ref "R3") (pin "2") (pinfunction "2_2") (pintype "passive"))
      (node (ref "R6") (pin "1") (pinfunction "1_1") (pintype "passive"))
      (node (ref "R7") (pin "1") (pinfunction "1_1") (pintype "passive"))
      (node (ref "RESET") (pin "3") (pinfunction "3_3") (pintype "passive"))
      (node (ref "RESET") (pin "4") (pinfunction "4_4") (pintype "passive"))
      (node (ref "RF-MOD") (pin "G@1") (pinfunction "2_G@1") (pintype "passive"))
      (node (ref "RF-MOD") (pin "G@2") (pinfunction "2_G@2") (pintype "passive"))
      (node (ref "RF-MOD") (pin "G@3") (pinfunction "2_G@3") (pintype "passive"))
      (node (ref "RF-MOD") (pin "G@4") (pinfunction "2_G@4") (pintype "passive"))
      (node (ref "S1") (pin "3") (pinfunction "P$1_3") (pintype "bidirectional"))
      (node (ref "S2") (pin "3") (pinfunction "P$1_3") (pintype "bidirectional"))
      (node (ref "SWD-HEADER") (pin "3") (pinfunction "GND_3") (pintype "bidirectional"))
      (node (ref "U$1") (pin "12") (pinfunction "V_SSA_12") (pintype "bidirectional"))
      (node (ref "U$1") (pin "18") (pinfunction "V_SS1_18") (pintype "bidirectional"))
      (node (ref "U$1") (pin "63") (pinfunction "V_SS2_63") (pintype "bidirectional"))
      (node (ref "U$3") (pin "10") (pinfunction "GND-PIN1_10") (pintype "bidirectional"))
      (node (ref "U$3") (pin "17") (pinfunction "GND-PIN2_17") (pintype "bidirectional"))
      (node (ref "U$3") (pin "21") (pinfunction "GNS-PIN3_21") (pintype "bidirectional"))
      (node (ref "U$3") (pin "23") (pinfunction "GNG-PIN4_23") (pintype "bidirectional"))
      (node (ref "U$3") (pin "EXPOSED-PAD") (pinfunction "GND-BASE_EXPOSED-PAD") (pintype "bidirectional"))
      (node (ref "U$4") (pin "1") (pinfunction "INN_1") (pintype "bidirectional"))
      (node (ref "U$5") (pin "1") (pinfunction "INN_1") (pintype "bidirectional"))
      (node (ref "USART1") (pin "1") (pinfunction "1_1") (pintype "passive"))
    )
    (net (code "50") (name "Net-(3V3-REG-VO-Pad2)") (class "Default")
      (node (ref "3V3-REG") (pin "2") (pinfunction "VO_2") (pintype "passive"))
      (node (ref "3V3-REG") (pin "4") (pinfunction "VO_4") (pintype "bidirectional"))
      (node (ref "C35") (pin "1") (pinfunction "1_1") (pintype "passive"))
      (node (ref "JP1") (pin "1") (pinfunction "1_1") (pintype "passive"))
    )
    (net (code "51") (name "Net-(5V-REG-VO-Pad2)") (class "Default")
      (node (ref "5V-REG") (pin "2") (pinfunction "VO_2") (pintype "passive"))
      (node (ref "5V-REG") (pin "4") (pinfunction "VO_4") (pintype "bidirectional"))
      (node (ref "C43") (pin "1") (pinfunction "1_1") (pintype "passive"))
      (node (ref "JP2") (pin "1") (pinfunction "1_1") (pintype "passive"))
    )
    (net (code "52") (name "Net-(10MHZ-OUTPUT)") (class "Default")
      (node (ref "10MHZ") (pin "3") (pinfunction "OUTPUT_3") (pintype "bidirectional"))
      (node (ref "C6") (pin "1") (pinfunction "1_1") (pintype "passive"))
    )
    (net (code "53") (name "Net-(C2-Pad1)") (class "Default")
      (node (ref "C2") (pin "1") (pinfunction "1_1") (pintype "passive"))
      (node (ref "Q1") (pin "2") (pinfunction "2_2") (pintype "passive"))
      (node (ref "R1") (pin "2") (pinfunction "2_2") (pintype "passive"))
    )
    (net (code "54") (name "Net-(C3-Pad1)") (class "Default")
      (node (ref "C3") (pin "1") (pinfunction "1_1") (pintype "passive"))
      (node (ref "Q1") (pin "1") (pinfunction "1_1") (pintype "passive"))
      (node (ref "R2") (pin "2") (pinfunction "2_2") (pintype "passive"))
    )
    (net (code "55") (name "Net-(C4-Pad2)") (class "Default")
      (node (ref "C4") (pin "2") (pinfunction "2_2") (pintype "passive"))
      (node (ref "R7") (pin "2") (pinfunction "2_2") (pintype "passive"))
    )
    (net (code "56") (name "Net-(C37-Pad2)") (class "Default")
      (node (ref "C37") (pin "2") (pinfunction "2_2") (pintype "passive"))
      (node (ref "R4") (pin "2") (pinfunction "2_2") (pintype "passive"))
      (node (ref "R9") (pin "1") (pinfunction "1_1") (pintype "passive"))
    )
    (net (code "57") (name "Net-(C39-Pad2)") (class "Default")
      (node (ref "C39") (pin "2") (pinfunction "2_2") (pintype "passive"))
      (node (ref "R10") (pin "1") (pinfunction "1_1") (pintype "passive"))
      (node (ref "R5") (pin "2") (pinfunction "2_2") (pintype "passive"))
    )
    (net (code "58") (name "Net-(C_I-Pad2)") (class "Default")
      (node (ref "C_I") (pin "2") (pinfunction "2_2") (pintype "passive"))
      (node (ref "R_Z") (pin "2") (pinfunction "2_2") (pintype "passive"))
    )
    (net (code "59") (name "Net-(DAC1-COMP1)") (class "Default")
      (node (ref "C8") (pin "1") (pinfunction "1_1") (pintype "passive"))
      (node (ref "DAC1") (pin "19") (pinfunction "COMP1_19") (pintype "bidirectional"))
    )
    (net (code "60") (name "Net-(DAC1-COMP2)") (class "Default")
      (node (ref "C9") (pin "1") (pinfunction "1_1") (pintype "passive"))
      (node (ref "DAC1") (pin "23") (pinfunction "COMP2_23") (pintype "bidirectional"))
    )
    (net (code "61") (name "Net-(DAC1-EXTIO)") (class "Default")
      (node (ref "C12") (pin "2") (pinfunction "2_2") (pintype "passive"))
      (node (ref "DAC1") (pin "17") (pinfunction "EXTIO_17") (pintype "bidirectional"))
    )
    (net (code "62") (name "Net-(DAC1-I_OUT)") (class "Default")
      (node (ref "DAC1") (pin "22") (pinfunction "I_OUT_22") (pintype "bidirectional"))
      (node (ref "IC2") (pin "3") (pinfunction "+IN_3") (pintype "input"))
      (node (ref "R3") (pin "1") (pinfunction "1_1") (pintype "passive"))
    )
    (net (code "63") (name "Net-(DAC2-COMP1)") (class "Default")
      (node (ref "C10") (pin "1") (pinfunction "1_1") (pintype "passive"))
      (node (ref "DAC2") (pin "19") (pinfunction "COMP1_19") (pintype "bidirectional"))
    )
    (net (code "64") (name "Net-(DAC2-COMP2)") (class "Default")
      (node (ref "C11") (pin "1") (pinfunction "1_1") (pintype "passive"))
      (node (ref "DAC2") (pin "23") (pinfunction "COMP2_23") (pintype "bidirectional"))
    )
    (net (code "65") (name "Net-(DAC2-EXTIO)") (class "Default")
      (node (ref "C13") (pin "2") (pinfunction "2_2") (pintype "passive"))
      (node (ref "DAC2") (pin "17") (pinfunction "EXTIO_17") (pintype "bidirectional"))
    )
    (net (code "66") (name "Net-(DAC2-I_OUT)") (class "Default")
      (node (ref "DAC2") (pin "22") (pinfunction "I_OUT_22") (pintype "bidirectional"))
      (node (ref "IC2") (pin "5") (pinfunction "+IN_5") (pintype "input"))
      (node (ref "R6") (pin "2") (pinfunction "2_2") (pintype "passive"))
    )
    (net (code "67") (name "Net-(IC1-+IN)") (class "Default")
      (node (ref "IC1") (pin "1") (pinfunction "+IN_1") (pintype "input"))
      (node (ref "R11") (pin "1") (pinfunction "1_1") (pintype "passive"))
      (node (ref "R12") (pin "2") (pinfunction "2_2") (pintype "passive"))
    )
    (net (code "68") (name "Net-(IC2A--IN)") (class "Default")
      (node (ref "IC2") (pin "1") (pinfunction "OUT_1") (pintype "output"))
      (node (ref "IC2") (pin "2") (pinfunction "-IN_2") (pintype "input"))
      (node (ref "I_BUF") (pin "TP") (pinfunction "TP_TP") (pintype "input"))
      (node (ref "R4") (pin "1") (pinfunction "1_1") (pintype "passive"))
    )
    (net (code "69") (name "Net-(IC2B--IN)") (class "Default")
      (node (ref "IC2") (pin "6") (pinfunction "-IN_6") (pintype "input"))
      (node (ref "IC2") (pin "7") (pinfunction "OUT_7") (pintype "output"))
      (node (ref "Q_BUF") (pin "TP") (pinfunction "TP_TP") (pintype "input"))
      (node (ref "R5") (pin "1") (pinfunction "1_1") (pintype "passive"))
    )
    (net (code "70") (name "Net-(IC3-CAP+)") (class "Default")
      (node (ref "C41") (pin "+") (pinfunction "+_+") (pintype "passive"))
      (node (ref "IC3") (pin "2") (pinfunction "CAP+_2") (pintype "passive"))
    )
    (net (code "71") (name "Net-(IC3-CAP-)") (class "Default")
      (node (ref "C41") (pin "-") (pinfunction "-_-") (pintype "passive"))
      (node (ref "IC3") (pin "4") (pinfunction "CAP-_4") (pintype "passive"))
    )
    (net (code "72") (name "Net-(S1-P$2)") (class "Default")
      (node (ref "RS1") (pin "1") (pinfunction "1_1") (pintype "passive"))
      (node (ref "S1") (pin "1") (pinfunction "P$2_1") (pintype "bidirectional"))
    )
    (net (code "73") (name "Net-(S1-P$3)") (class "Default")
      (node (ref "RS2") (pin "1") (pinfunction "1_1") (pintype "passive"))
      (node (ref "S1") (pin "2") (pinfunction "P$3_2") (pintype "bidirectional"))
    )
    (net (code "74") (name "Net-(S2-P$2)") (class "Default")
      (node (ref "RS3") (pin "1") (pinfunction "1_1") (pintype "passive"))
      (node (ref "S2") (pin "1") (pinfunction "P$2_1") (pintype "bidirectional"))
    )
    (net (code "75") (name "Net-(S2-P$3)") (class "Default")
      (node (ref "RS4") (pin "1") (pinfunction "1_1") (pintype "passive"))
      (node (ref "S2") (pin "2") (pinfunction "P$3_2") (pintype "bidirectional"))
    )
    (net (code "76") (name "Net-(U$1B-PH0)") (class "Default")
      (node (ref "R1") (pin "1") (pinfunction "1_1") (pintype "passive"))
      (node (ref "U$1") (pin "5") (pinfunction "PH0_5") (pintype "bidirectional"))
    )
    (net (code "77") (name "Net-(U$1B-PH1)") (class "Default")
      (node (ref "R2") (pin "1") (pinfunction "1_1") (pintype "passive"))
      (node (ref "U$1") (pin "6") (pinfunction "PH1_6") (pintype "bidirectional"))
    )
    (net (code "78") (name "Net-(U$1F-V_CAP_1)") (class "Default")
      (node (ref "C21") (pin "1") (pinfunction "1_1") (pintype "passive"))
      (node (ref "U$1") (pin "31") (pinfunction "V_CAP_1_31") (pintype "bidirectional"))
    )
    (net (code "79") (name "Net-(U$1F-V_CAP_2)") (class "Default")
      (node (ref "C22") (pin "1") (pinfunction "1_1") (pintype "passive"))
      (node (ref "U$1") (pin "47") (pinfunction "V_CAP_2_47") (pintype "bidirectional"))
    )
    (net (code "80") (name "Net-(U$3-BB)") (class "Default")
      (node (ref "C34") (pin "1") (pinfunction "1_1") (pintype "passive"))
      (node (ref "U$3") (pin "14") (pinfunction "BB_14") (pintype "bidirectional"))
    )
    (net (code "81") (name "Net-(U$3-CMA)") (class "Default")
      (node (ref "C1") (pin "2") (pinfunction "2_2") (pintype "passive"))
      (node (ref "U$3") (pin "16") (pinfunction "TB_16") (pintype "bidirectional"))
      (node (ref "U$3") (pin "18") (pinfunction "CMC_18") (pintype "bidirectional"))
      (node (ref "U$3") (pin "19") (pinfunction "CMB_19") (pintype "bidirectional"))
      (node (ref "U$3") (pin "20") (pinfunction "CMA_20") (pintype "bidirectional"))
    )
    (net (code "82") (name "Net-(U$3-CP)") (class "Default")
      (node (ref "C_P") (pin "2") (pinfunction "2_2") (pintype "passive"))
      (node (ref "R_Z") (pin "1") (pinfunction "1_1") (pintype "passive"))
      (node (ref "TUNE") (pin "TP") (pinfunction "TP_TP") (pintype "input"))
      (node (ref "U$3") (pin "15") (pinfunction "TUNE_15") (pintype "bidirectional"))
      (node (ref "U$3") (pin "25") (pinfunction "CP_25") (pintype "bidirectional"))
    )
    (net (code "83") (name "Net-(U$3-REF+)") (class "Default")
      (node (ref "C6") (pin "2") (pinfunction "2_2") (pintype "passive"))
      (node (ref "U$3") (pin "27") (pinfunction "REF+_27") (pintype "bidirectional"))
    )
    (net (code "84") (name "Net-(U$3-REF-)") (class "Default")
      (node (ref "C7") (pin "2") (pinfunction "2_2") (pintype "passive"))
      (node (ref "U$3") (pin "28") (pinfunction "REF-_28") (pintype "bidirectional"))
    )
    (net (code "85") (name "Net-(U$3-RF+)") (class "Default")
      (node (ref "C4") (pin "1") (pinfunction "1_1") (pintype "passive"))
      (node (ref "L2") (pin "2") (pinfunction "2_2") (pintype "passive"))
      (node (ref "U$3") (pin "12") (pinfunction "RF+_12") (pintype "bidirectional"))
    )
    (net (code "86") (name "Net-(U$3-RF-)") (class "Default")
      (node (ref "C5") (pin "1") (pinfunction "1_1") (pintype "passive"))
      (node (ref "L1") (pin "2") (pinfunction "2_2") (pintype "passive"))
      (node (ref "U$3") (pin "11") (pinfunction "RF-_11") (pintype "bidirectional"))
    )
    (net (code "87") (name "Net-(U$3-V_VCO+)") (class "Default")
      (node (ref "R8") (pin "1") (pinfunction "1_1") (pintype "passive"))
      (node (ref "U$3") (pin "22") (pinfunction "V_VCO+_22") (pintype "bidirectional"))
    )
    (net (code "88") (name "Net-(U$4-+OUT)") (class "Default")
      (node (ref "JP6") (pin "2") (pinfunction "2_2") (pintype "passive"))
      (node (ref "U$4") (pin "4") (pinfunction "+OUT_4") (pintype "bidirectional"))
    )
    (net (code "89") (name "Net-(U$4--OUT)") (class "Default")
      (node (ref "JP7") (pin "1") (pinfunction "1_1") (pintype "passive"))
      (node (ref "U$4") (pin "5") (pinfunction "-OUT_5") (pintype "bidirectional"))
    )
    (net (code "90") (name "Net-(U$4-INP)") (class "Default")
      (node (ref "C38") (pin "2") (pinfunction "2_2") (pintype "passive"))
      (node (ref "R9") (pin "2") (pinfunction "2_2") (pintype "passive"))
      (node (ref "U$4") (pin "8") (pinfunction "INP_8") (pintype "bidirectional"))
    )
    (net (code "91") (name "Net-(U$5-+OUT)") (class "Default")
      (node (ref "JP9") (pin "1") (pinfunction "1_1") (pintype "passive"))
      (node (ref "U$5") (pin "4") (pinfunction "+OUT_4") (pintype "bidirectional"))
    )
    (net (code "92") (name "Net-(U$5--OUT)") (class "Default")
      (node (ref "JP8") (pin "2") (pinfunction "2_2") (pintype "passive"))
      (node (ref "U$5") (pin "5") (pinfunction "-OUT_5") (pintype "bidirectional"))
    )
    (net (code "93") (name "Net-(U$5-INP)") (class "Default")
      (node (ref "C40") (pin "2") (pinfunction "2_2") (pintype "passive"))
      (node (ref "R10") (pin "2") (pinfunction "2_2") (pintype "passive"))
      (node (ref "U$5") (pin "8") (pinfunction "INP_8") (pintype "bidirectional"))
    )
    (net (code "94") (name "unconnected-(DAC1-BIASJ-Pad18)") (class "Default")
      (node (ref "DAC1") (pin "18") (pinfunction "BIASJ_18") (pintype "bidirectional"))
    )
    (net (code "95") (name "unconnected-(DAC2-BIASJ-Pad18)") (class "Default")
      (node (ref "DAC2") (pin "18") (pinfunction "BIASJ_18") (pintype "bidirectional"))
    )
    (net (code "96") (name "unconnected-(IC3-NC-Pad1)") (class "Default")
      (node (ref "IC3") (pin "1") (pinfunction "NC_1") (pintype "no_connect"))
    )
    (net (code "97") (name "unconnected-(IC3-OSC-Pad7)") (class "Default")
      (node (ref "IC3") (pin "7") (pinfunction "OSC_7") (pintype "output"))
    )
    (net (code "98") (name "unconnected-(IQ_MOD-EN-Pad1)") (class "Default")
      (node (ref "IQ_MOD") (pin "1") (pinfunction "EN_1") (pintype "bidirectional"))
    )
    (net (code "99") (name "unconnected-(SWD-HEADER-SWO(RESERVED)-Pad6)") (class "Default")
      (node (ref "SWD-HEADER") (pin "6") (pinfunction "SWO(RESERVED)_6") (pintype "bidirectional"))
    )
    (net (code "100") (name "unconnected-(U$1B-PD2-Pad54)") (class "Default")
      (node (ref "U$1") (pin "54") (pinfunction "PD2_54") (pintype "bidirectional"))
    )
    (net (code "101") (name "unconnected-(U$1C-PA0-Pad14)") (class "Default")
      (node (ref "U$1") (pin "14") (pinfunction "PA0_14") (pintype "bidirectional"))
    )
    (net (code "102") (name "unconnected-(U$1C-PA1-Pad15)") (class "Default")
      (node (ref "U$1") (pin "15") (pinfunction "PA1_15") (pintype "bidirectional"))
    )
    (net (code "103") (name "unconnected-(U$1C-PA3-Pad17)") (class "Default")
      (node (ref "U$1") (pin "17") (pinfunction "PA3_17") (pintype "bidirectional"))
    )
    (net (code "104") (name "unconnected-(U$1C-PA8-Pad41)") (class "Default")
      (node (ref "U$1") (pin "41") (pinfunction "PA8_41") (pintype "bidirectional"))
    )
    (net (code "105") (name "unconnected-(U$1C-PA15-Pad50)") (class "Default")
      (node (ref "U$1") (pin "50") (pinfunction "PA15_50") (pintype "bidirectional"))
    )
    (net (code "106") (name "unconnected-(U$1D-PB3-Pad55)") (class "Default")
      (node (ref "U$1") (pin "55") (pinfunction "PB3_55") (pintype "bidirectional"))
    )
    (net (code "107") (name "unconnected-(U$1D-PB4-Pad56)") (class "Default")
      (node (ref "U$1") (pin "56") (pinfunction "PB4_56") (pintype "bidirectional"))
    )
    (net (code "108") (name "unconnected-(U$1D-PB5-Pad57)") (class "Default")
      (node (ref "U$1") (pin "57") (pinfunction "PB5_57") (pintype "bidirectional"))
    )
    (net (code "109") (name "unconnected-(U$1D-PB6-Pad58)") (class "Default")
      (node (ref "U$1") (pin "58") (pinfunction "PB6_58") (pintype "bidirectional"))
    )
    (net (code "110") (name "unconnected-(U$1D-PB7-Pad59)") (class "Default")
      (node (ref "U$1") (pin "59") (pinfunction "PB7_59") (pintype "bidirectional"))
    )
    (net (code "111") (name "unconnected-(U$1D-PB8-Pad61)") (class "Default")
      (node (ref "U$1") (pin "61") (pinfunction "PB8_61") (pintype "bidirectional"))
    )
    (net (code "112") (name "unconnected-(U$1D-PB9-Pad62)") (class "Default")
      (node (ref "U$1") (pin "62") (pinfunction "PB9_62") (pintype "bidirectional"))
    )
    (net (code "113") (name "unconnected-(U$1D-PB11-Pad30)") (class "Default")
      (node (ref "U$1") (pin "30") (pinfunction "PB11_30") (pintype "bidirectional"))
    )
    (net (code "114") (name "unconnected-(U$1F-V_BAT-Pad1)") (class "Default")
      (node (ref "U$1") (pin "1") (pinfunction "V_BAT_1") (pintype "bidirectional"))
    )
    (net (code "115") (name "unconnected-(U$3-REFO-Pad2)") (class "Default")
      (node (ref "U$3") (pin "2") (pinfunction "REFO_2") (pintype "bidirectional"))
    )
  )
)
